# rapidshark-main-breakout-top-mk-1_A.net
KiCad netlist of a schematic drawn in EAGLE
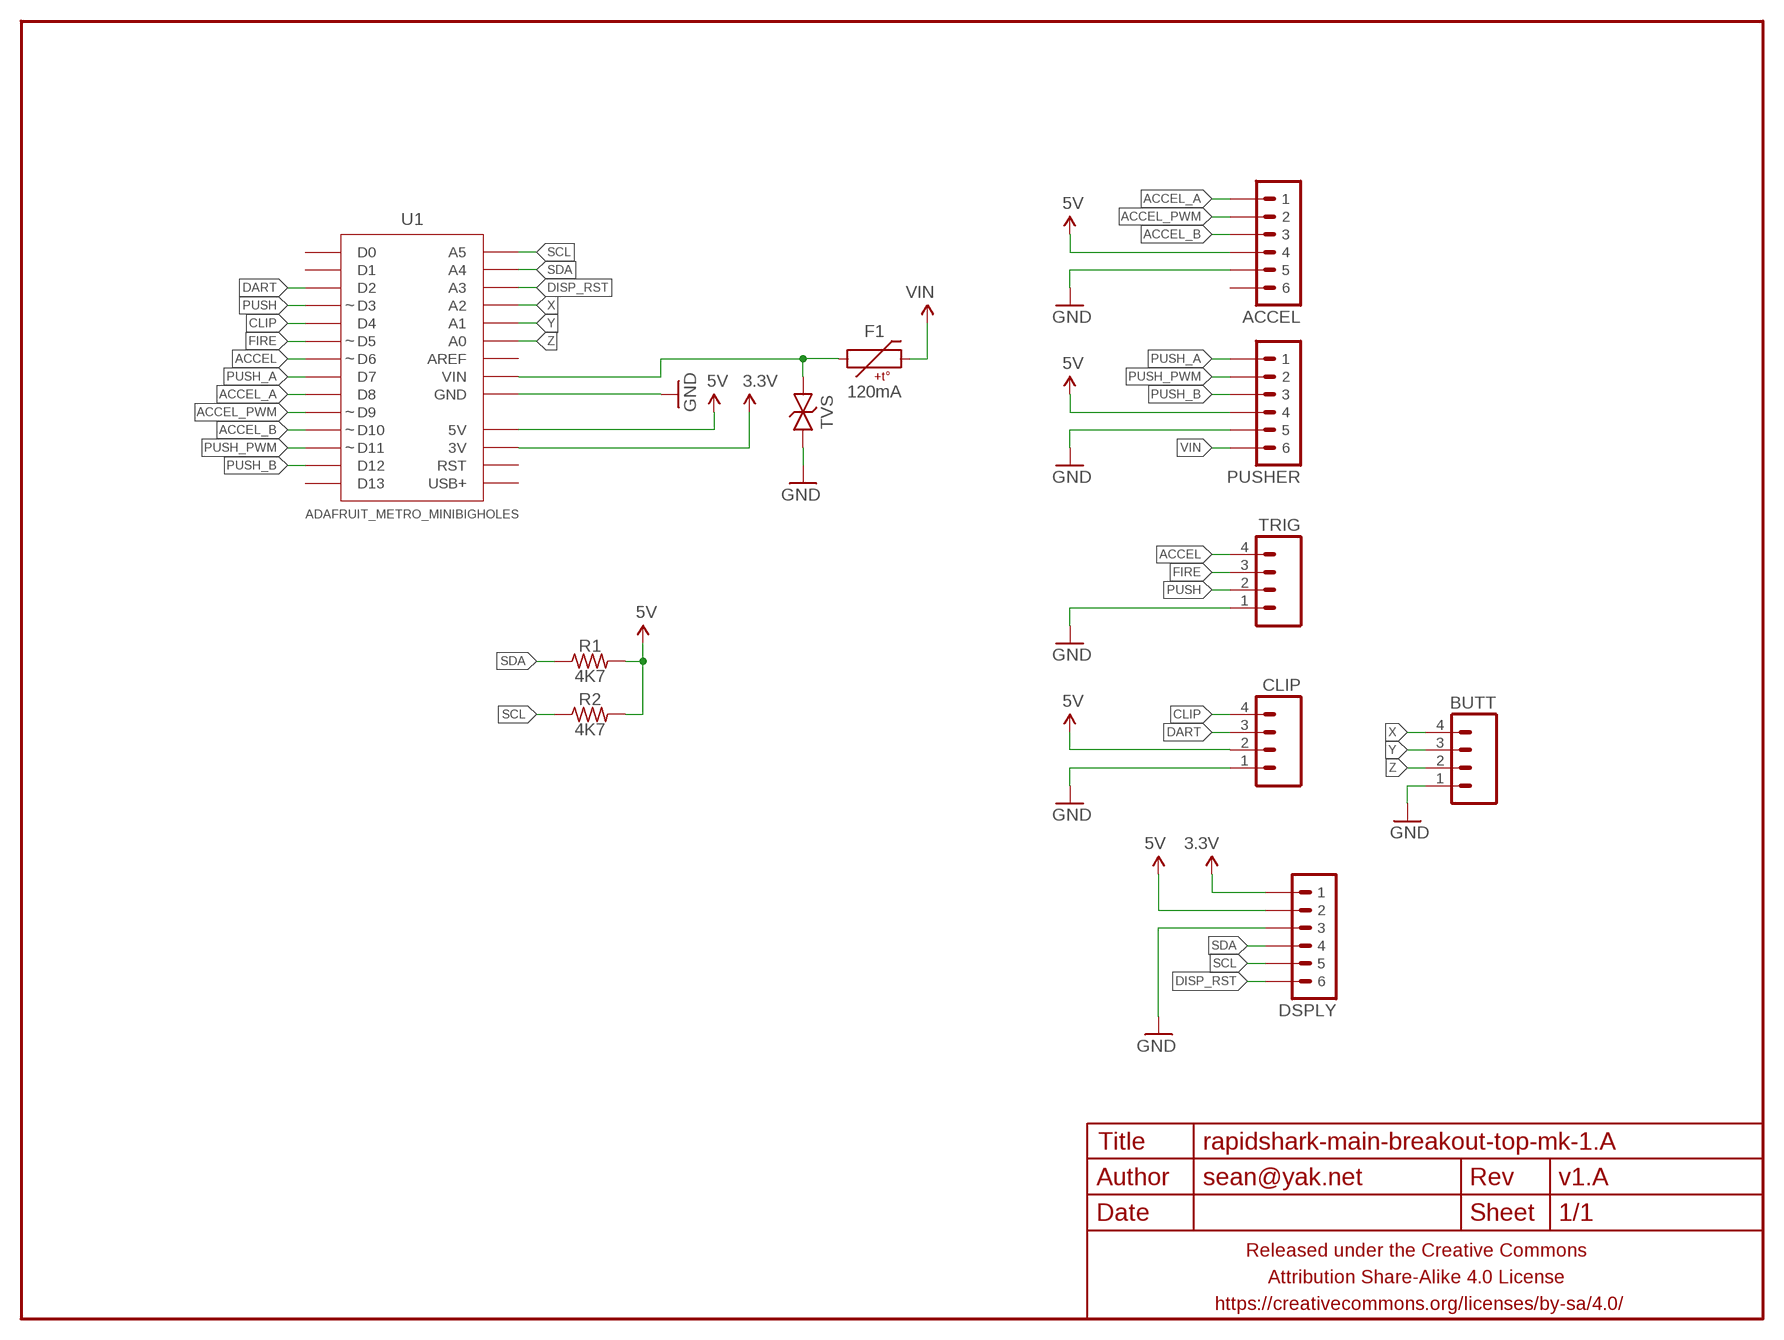
[diagram p0: schematic, sheet 1]

(export (version "E")
  (design (tool "Eeschema 10.0.6"))
  (components
    (comp (ref "ACCEL")
      (value "M06JST-PH-PTH-VERT")
      (footprint "eagle-import:JST-6-PH-VERT-PTH")
      (libsource (lib "eagle-import") (part "M06JST-PH-PTH-VERT"))
    )
    (comp (ref "BUTT")
      (value "M04JST-PTH-VERT")
      (footprint "eagle-import:JST-4-PH-VERT-PTH")
      (libsource (lib "eagle-import") (part "M04JST-PTH-VERT"))
    )
    (comp (ref "CLIP")
      (value "M04JST-PTH-VERT")
      (footprint "eagle-import:JST-4-PH-VERT-PTH")
      (libsource (lib "eagle-import") (part "M04JST-PTH-VERT"))
    )
    (comp (ref "DSPLY")
      (value "M06JST-PH-PTH-VERT")
      (footprint "eagle-import:JST-6-PH-VERT-PTH")
      (libsource (lib "eagle-import") (part "M06JST-PH-PTH-VERT"))
    )
    (comp (ref "F1")
      (value "120mA")
      (footprint "eagle-import:PTC-1206")
      (libsource (lib "eagle-import") (part "PTCSMD"))
    )
    (comp (ref "FRAME1")
      (value "FRAME-LETTERNO_PACKAGE")
      (footprint "eagle-import:DUMMY")
      (fields (field (name "DESIGNER") "sean@yak.net") (field (name "VERSION") "v1.A"))
      (libsource (lib "eagle-import") (part "FRAME-LETTERNO_PACKAGE"))
    )
    (comp (ref "PUSHER")
      (value "M06JST-PH-PTH-VERT")
      (footprint "eagle-import:JST-6-PH-VERT-PTH")
      (libsource (lib "eagle-import") (part "M06JST-PH-PTH-VERT"))
    )
    (comp (ref "R1")
      (value "4K7")
      (footprint "eagle-import:R0805")
      (libsource (lib "eagle-import") (part "RESISTORR0805"))
    )
    (comp (ref "R2")
      (value "4K7")
      (footprint "eagle-import:R0805")
      (libsource (lib "eagle-import") (part "RESISTORR0805"))
    )
    (comp (ref "TRIG")
      (value "M04JST-PTH-VERT")
      (footprint "eagle-import:JST-4-PH-VERT-PTH")
      (libsource (lib "eagle-import") (part "M04JST-PTH-VERT"))
    )
    (comp (ref "TVS")
      (value "TVSSMA")
      (footprint "eagle-import:SMA-DIODE-TVS-BIDIR")
      (libsource (lib "eagle-import") (part "TVSSMA"))
    )
    (comp (ref "U1")
      (value "ADAFRUIT_METRO_MINIBIGHOLES")
      (footprint "eagle-import:ADAFRUIT_METRO_MINI_BIGHOLES")
      (libsource (lib "eagle-import") (part "ADAFRUIT_METRO_MINIBIGHOLES"))
    )
  )
  (nets
    (net (code "1") (name "3.3V") (class "Default")
      (node (ref "DSPLY") (pin "1") (pinfunction "1_1") (pintype "passive"))
      (node (ref "U1") (pin "17") (pinfunction "3V_17") (pintype "bidirectional"))
    )
    (net (code "2") (name "5V") (class "Default")
      (node (ref "ACCEL") (pin "4") (pinfunction "4_4") (pintype "passive"))
      (node (ref "CLIP") (pin "2") (pinfunction "2_2") (pintype "passive"))
      (node (ref "DSPLY") (pin "2") (pinfunction "2_2") (pintype "passive"))
      (node (ref "PUSHER") (pin "4") (pinfunction "4_4") (pintype "passive"))
      (node (ref "R1") (pin "2") (pinfunction "2_2") (pintype "passive"))
      (node (ref "R2") (pin "2") (pinfunction "2_2") (pintype "passive"))
      (node (ref "U1") (pin "18") (pinfunction "5V_18") (pintype "bidirectional"))
    )
    (net (code "3") (name "ACCEL") (class "Default")
      (node (ref "TRIG") (pin "4") (pinfunction "4_4") (pintype "passive"))
      (node (ref "U1") (pin "7") (pinfunction "D6_7") (pintype "bidirectional"))
    )
    (net (code "4") (name "ACCEL_A") (class "Default")
      (node (ref "ACCEL") (pin "1") (pinfunction "1_1") (pintype "passive"))
      (node (ref "U1") (pin "9") (pinfunction "D8_9") (pintype "bidirectional"))
    )
    (net (code "5") (name "ACCEL_B") (class "Default")
      (node (ref "ACCEL") (pin "3") (pinfunction "3_3") (pintype "passive"))
      (node (ref "U1") (pin "11") (pinfunction "D10_11") (pintype "bidirectional"))
    )
    (net (code "6") (name "ACCEL_PWM") (class "Default")
      (node (ref "ACCEL") (pin "2") (pinfunction "2_2") (pintype "passive"))
      (node (ref "U1") (pin "10") (pinfunction "D9_10") (pintype "bidirectional"))
    )
    (net (code "7") (name "CLIP") (class "Default")
      (node (ref "CLIP") (pin "4") (pinfunction "4_4") (pintype "passive"))
      (node (ref "U1") (pin "5") (pinfunction "D4_5") (pintype "bidirectional"))
    )
    (net (code "8") (name "DART") (class "Default")
      (node (ref "CLIP") (pin "3") (pinfunction "3_3") (pintype "passive"))
      (node (ref "U1") (pin "3") (pinfunction "D2_3") (pintype "bidirectional"))
    )
    (net (code "9") (name "DISP_RST") (class "Default")
      (node (ref "DSPLY") (pin "6") (pinfunction "6_6") (pintype "passive"))
      (node (ref "U1") (pin "26") (pinfunction "A3_26") (pintype "bidirectional"))
    )
    (net (code "10") (name "FIRE") (class "Default")
      (node (ref "TRIG") (pin "3") (pinfunction "3_3") (pintype "passive"))
      (node (ref "U1") (pin "6") (pinfunction "D5_6") (pintype "bidirectional"))
    )
    (net (code "11") (name "GND") (class "Default")
      (node (ref "ACCEL") (pin "5") (pinfunction "5_5") (pintype "passive"))
      (node (ref "BUTT") (pin "1") (pinfunction "1_1") (pintype "passive"))
      (node (ref "CLIP") (pin "1") (pinfunction "1_1") (pintype "passive"))
      (node (ref "DSPLY") (pin "3") (pinfunction "3_3") (pintype "passive"))
      (node (ref "PUSHER") (pin "5") (pinfunction "5_5") (pintype "passive"))
      (node (ref "TRIG") (pin "1") (pinfunction "1_1") (pintype "passive"))
      (node (ref "TVS") (pin "1") (pinfunction "1_1") (pintype "passive"))
      (node (ref "U1") (pin "19") (pinfunction "GND_19") (pintype "bidirectional"))
      (node (ref "U1") (pin "20") (pinfunction "GND_20") (pintype "bidirectional"))
    )
    (net (code "12") (name "Net-(U1-VIN)") (class "Default")
      (node (ref "F1") (pin "1") (pinfunction "1_1") (pintype "passive"))
      (node (ref "TVS") (pin "2") (pinfunction "2_2") (pintype "passive"))
      (node (ref "U1") (pin "21") (pinfunction "VIN_21") (pintype "bidirectional"))
    )
    (net (code "13") (name "PUSH") (class "Default")
      (node (ref "TRIG") (pin "2") (pinfunction "2_2") (pintype "passive"))
      (node (ref "U1") (pin "4") (pinfunction "D3_4") (pintype "bidirectional"))
    )
    (net (code "14") (name "PUSH_A") (class "Default")
      (node (ref "PUSHER") (pin "1") (pinfunction "1_1") (pintype "passive"))
      (node (ref "U1") (pin "8") (pinfunction "D7_8") (pintype "bidirectional"))
    )
    (net (code "15") (name "PUSH_B") (class "Default")
      (node (ref "PUSHER") (pin "3") (pinfunction "3_3") (pintype "passive"))
      (node (ref "U1") (pin "13") (pinfunction "D12_13") (pintype "bidirectional"))
    )
    (net (code "16") (name "PUSH_PWM") (class "Default")
      (node (ref "PUSHER") (pin "2") (pinfunction "2_2") (pintype "passive"))
      (node (ref "U1") (pin "12") (pinfunction "D11_12") (pintype "bidirectional"))
    )
    (net (code "17") (name "SCL") (class "Default")
      (node (ref "DSPLY") (pin "5") (pinfunction "5_5") (pintype "passive"))
      (node (ref "R2") (pin "1") (pinfunction "1_1") (pintype "passive"))
      (node (ref "U1") (pin "28") (pinfunction "A5_28") (pintype "bidirectional"))
    )
    (net (code "18") (name "SDA") (class "Default")
      (node (ref "DSPLY") (pin "4") (pinfunction "4_4") (pintype "passive"))
      (node (ref "R1") (pin "1") (pinfunction "1_1") (pintype "passive"))
      (node (ref "U1") (pin "27") (pinfunction "A4_27") (pintype "bidirectional"))
    )
    (net (code "19") (name "VIN") (class "Default")
      (node (ref "F1") (pin "2") (pinfunction "2_2") (pintype "passive"))
      (node (ref "PUSHER") (pin "6") (pinfunction "6_6") (pintype "passive"))
    )
    (net (code "20") (name "X") (class "Default")
      (node (ref "BUTT") (pin "4") (pinfunction "4_4") (pintype "passive"))
      (node (ref "U1") (pin "25") (pinfunction "A2_25") (pintype "bidirectional"))
    )
    (net (code "21") (name "Y") (class "Default")
      (node (ref "BUTT") (pin "3") (pinfunction "3_3") (pintype "passive"))
      (node (ref "U1") (pin "24") (pinfunction "A1_24") (pintype "bidirectional"))
    )
    (net (code "22") (name "Z") (class "Default")
      (node (ref "BUTT") (pin "2") (pinfunction "2_2") (pintype "passive"))
      (node (ref "U1") (pin "23") (pinfunction "A0_23") (pintype "bidirectional"))
    )
    (net (code "23") (name "unconnected-(ACCEL-Pad6)") (class "Default")
      (node (ref "ACCEL") (pin "6") (pinfunction "6_6") (pintype "passive"))
    )
    (net (code "24") (name "unconnected-(U1-AREF-Pad22)") (class "Default")
      (node (ref "U1") (pin "22") (pinfunction "AREF_22") (pintype "bidirectional"))
    )
    (net (code "25") (name "unconnected-(U1-D0-Pad1)") (class "Default")
      (node (ref "U1") (pin "1") (pinfunction "D0_1") (pintype "bidirectional"))
    )
    (net (code "26") (name "unconnected-(U1-D1-Pad2)") (class "Default")
      (node (ref "U1") (pin "2") (pinfunction "D1_2") (pintype "bidirectional"))
    )
    (net (code "27") (name "unconnected-(U1-D13-Pad14)") (class "Default")
      (node (ref "U1") (pin "14") (pinfunction "D13_14") (pintype "bidirectional"))
    )
    (net (code "28") (name "unconnected-(U1-RST-Pad16)") (class "Default")
      (node (ref "U1") (pin "16") (pinfunction "RST_16") (pintype "bidirectional"))
    )
    (net (code "29") (name "unconnected-(U1-USB+-Pad15)") (class "Default")
      (node (ref "U1") (pin "15") (pinfunction "USB+_15") (pintype "bidirectional"))
    )
  )
)
